# OUTPUT_CONNECTORS.net
KiCad netlist of a schematic drawn in Altium Designer
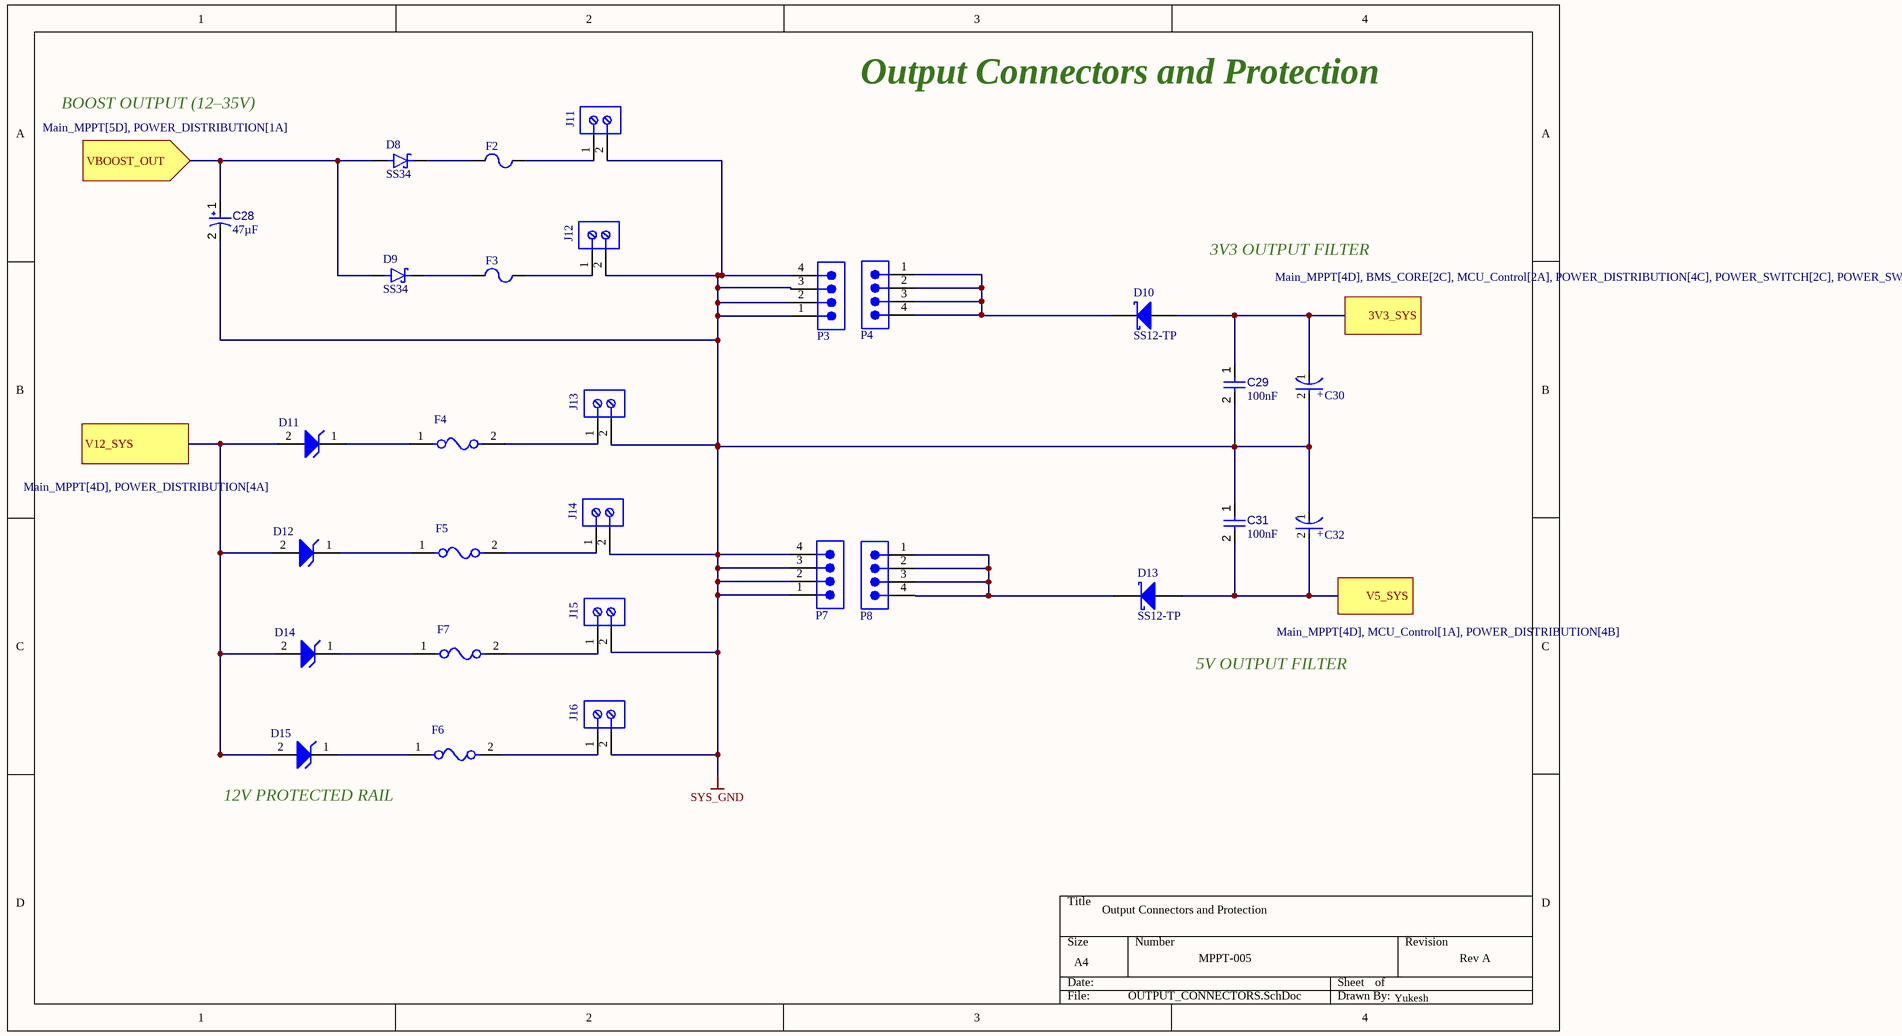
[diagram p0: OUTPUT_CONNECTORS.SchDoc]

(export (version "E")
  (design (tool "Eeschema 10.0.6"))
  (components
    (comp (ref "C28")
      (value "47µF")
      (footprint "CAPPR55-250-1120X630X1220")
      (description "Aluminum Electrolytic Capacitor, 47 uF, +/- 20%, 50 V, -40 to 85 degC, 2-Pin THD, RoHS, Bulk")
      (fields (field (name "MANUFACTURER") "Panasonic") (field (name "TOLERANCE") "20%"))
      (libsource (lib "YUKESH S") (part "CAP-P-2"))
    )
    (comp (ref "C29")
      (value "100nF")
      (footprint "CAPC0402(1005)60_L")
      (description "Chip Capacitor, 100nF +/-20%, 25V, 0402, Thickness 0.6 mm")
      (fields (field (name "TOLERANCE") "10%") (field (name "Comment") "Capacitor 100nF +/-20% 25V 0402"))
      (libsource (lib "YUKESH S") (part "CAP-NP-2"))
    )
    (comp (ref "C30")
      (value "F980J106MMA")
      (footprint "FP-F98M-MFG")
      (description "CAP TANT 10UF 20% 6.3V 0603")
      (fields
        (field (name "OCTOPART") "https://octopart.com/f980j106mma-nichicon-220777")
        (field (name "TOLERANCE") "20%")
      )
      (libsource (lib "Altium Content Vault") (part "cf48714ba7e38822c1575c7ec0b6d1f"))
    )
    (comp (ref "C31")
      (value "100nF")
      (footprint "CAPC0402(1005)60_L")
      (description "Chip Capacitor, 100nF +/-20%, 25V, 0402, Thickness 0.6 mm")
      (fields (field (name "TOLERANCE") "10%") (field (name "Comment") "Capacitor 100nF +/-20% 25V 0402"))
      (libsource (lib "YUKESH S") (part "CAP-NP-2"))
    )
    (comp (ref "C32")
      (value "F980J106MMA")
      (footprint "FP-F98M-MFG")
      (description "CAP TANT 10UF 20% 6.3V 0603")
      (fields
        (field (name "OCTOPART") "https://octopart.com/f980j106mma-nichicon-220777")
        (field (name "TOLERANCE") "20%")
      )
      (libsource (lib "Altium Content Vault") (part "cf48714ba7e38822c1575c7ec0b6d1f"))
    )
    (comp (ref "D8")
      (value "SS34")
      (footprint "Copy of DIOM7959X265N")
      (description "Diode Schottky 40 V 3A Surface Mount SMC (DO-214AB)")
      (fields (field (name "MF") "onsemi"))
      (libsource (lib "YUKESH S") (part "SS34"))
    )
    (comp (ref "D9")
      (value "SS34")
      (footprint "Copy of DIOM7959X265N")
      (description "Diode Schottky 40 V 3A Surface Mount SMC (DO-214AB)")
      (fields (field (name "MF") "onsemi"))
      (libsource (lib "YUKESH S") (part "SS34"))
    )
    (comp (ref "D10")
      (value "SS12-TP")
      (footprint "MCC-DO-214AC-2_V")
      (description "Schottky Rectifier, 20 V, 1 A, -55 to 125 degC, 2-Pin DO-214AC, RoHS, Tape and Reel")
      (fields (field (name "MANUFACTURER") "Micro Commercial Components"))
      (libsource (lib "YUKESH S") (part "DSKY-AK-2"))
    )
    (comp (ref "D11")
      (value "824500600")
      (footprint "WE-TVSP_DO-214AC_Unidirectional")
      (description "TVS diode [Würth Elektronik] 824500600 TVS diode")
      (libsource (lib "Altium Content Vault") (part "WE-TVSP_Unidirectional"))
    )
    (comp (ref "D12")
      (value "824500600")
      (footprint "WE-TVSP_DO-214AC_Unidirectional")
      (description "TVS diode [Würth Elektronik] 824500600 TVS diode")
      (libsource (lib "Altium Content Vault") (part "WE-TVSP_Unidirectional"))
    )
    (comp (ref "D13")
      (value "SS12-TP")
      (footprint "MCC-DO-214AC-2_V")
      (description "Schottky Rectifier, 20 V, 1 A, -55 to 125 degC, 2-Pin DO-214AC, RoHS, Tape and Reel")
      (fields (field (name "MANUFACTURER") "Micro Commercial Components"))
      (libsource (lib "YUKESH S") (part "DSKY-AK-2"))
    )
    (comp (ref "D14")
      (value "824500600")
      (footprint "WE-TVSP_DO-214AC_Unidirectional")
      (description "TVS diode [Würth Elektronik] 824500600 TVS diode")
      (libsource (lib "Altium Content Vault") (part "WE-TVSP_Unidirectional"))
    )
    (comp (ref "D15")
      (value "824500600")
      (footprint "WE-TVSP_DO-214AC_Unidirectional")
      (description "TVS diode [Würth Elektronik] 824500600 TVS diode")
      (libsource (lib "Altium Content Vault") (part "WE-TVSP_Unidirectional"))
    )
    (comp (ref "F2")
      (value "0154001.DR")
      (footprint "LFUS-0154001.DR_V")
      (description "Very Fast-Acting Fuse, 1 A, -55 to 125 degC, 2-Pin SMD, RoHS, Tape and Reel")
      (fields (field (name "MANUFACTURER") "Littelfuse"))
      (libsource (lib "Altium Content Vault") (part "FUSE-2"))
    )
    (comp (ref "F3")
      (value "0154001.DR")
      (footprint "LFUS-0154001.DR_V")
      (description "Very Fast-Acting Fuse, 1 A, -55 to 125 degC, 2-Pin SMD, RoHS, Tape and Reel")
      (fields (field (name "MANUFACTURER") "Littelfuse"))
      (libsource (lib "Altium Content Vault") (part "FUSE-2"))
    )
    (comp (ref "F4")
      (value "02810005H")
      (footprint "FP-02810005H-MFG")
      (description "FUSE HLDR RADIAL 125V 5A PNL MNT")
      (fields
        (field (name "OCTOPART") "https://octopart.com/02810005h-littelfuse-557282")
        (field (name "MANUFACTURER") "Littelfuse")
      )
      (libsource (lib "Altium Content Vault") (part "5bcf9b9f640e542cf0359d10258e979"))
    )
    (comp (ref "F5")
      (value "02810005H")
      (footprint "FP-02810005H-MFG")
      (description "FUSE HLDR RADIAL 125V 5A PNL MNT")
      (fields
        (field (name "OCTOPART") "https://octopart.com/02810005h-littelfuse-557282")
        (field (name "MANUFACTURER") "Littelfuse")
      )
      (libsource (lib "Altium Content Vault") (part "5bcf9b9f640e542cf0359d10258e979"))
    )
    (comp (ref "F6")
      (value "02810005H")
      (footprint "FP-02810005H-MFG")
      (description "FUSE HLDR RADIAL 125V 5A PNL MNT")
      (fields
        (field (name "OCTOPART") "https://octopart.com/02810005h-littelfuse-557282")
        (field (name "MANUFACTURER") "Littelfuse")
      )
      (libsource (lib "Altium Content Vault") (part "5bcf9b9f640e542cf0359d10258e979"))
    )
    (comp (ref "F7")
      (value "02810005H")
      (footprint "FP-02810005H-MFG")
      (description "FUSE HLDR RADIAL 125V 5A PNL MNT")
      (fields
        (field (name "OCTOPART") "https://octopart.com/02810005h-littelfuse-557282")
        (field (name "MANUFACTURER") "Littelfuse")
      )
      (libsource (lib "Altium Content Vault") (part "5bcf9b9f640e542cf0359d10258e979"))
    )
    (comp (ref "J11")
      (value "1714955")
      (footprint "PHOE-1714955_V")
      (description "PC Terminal Block, Pitch 6.35 mm, 1 x 2 Position, Height 21.5 mm, Tail Lenght 5.1 mm, RoHS, Bulk")
      (fields (field (name "MANUFACTURER") "Phoenix Contact"))
      (libsource (lib "") (part "CN-1P-F-TB2_1"))
    )
    (comp (ref "J12")
      (value "1714955")
      (footprint "PHOE-1714955_V")
      (description "PC Terminal Block, Pitch 6.35 mm, 1 x 2 Position, Height 21.5 mm, Tail Lenght 5.1 mm, RoHS, Bulk")
      (fields (field (name "MANUFACTURER") "Phoenix Contact"))
      (libsource (lib "Altium Content Vault") (part "CN-1P-F-TB2"))
    )
    (comp (ref "J13")
      (value "1714955")
      (footprint "PHOE-1714955_V")
      (description "PC Terminal Block, Pitch 6.35 mm, 1 x 2 Position, Height 21.5 mm, Tail Lenght 5.1 mm, RoHS, Bulk")
      (fields (field (name "MANUFACTURER") "Phoenix Contact"))
      (libsource (lib "Altium Content Vault") (part "CN-1P-F-TB2"))
    )
    (comp (ref "J14")
      (value "1714955")
      (footprint "PHOE-1714955_V")
      (description "PC Terminal Block, Pitch 6.35 mm, 1 x 2 Position, Height 21.5 mm, Tail Lenght 5.1 mm, RoHS, Bulk")
      (fields (field (name "MANUFACTURER") "Phoenix Contact"))
      (libsource (lib "Altium Content Vault") (part "CN-1P-F-TB2"))
    )
    (comp (ref "J15")
      (value "1714955")
      (footprint "PHOE-1714955_V")
      (description "PC Terminal Block, Pitch 6.35 mm, 1 x 2 Position, Height 21.5 mm, Tail Lenght 5.1 mm, RoHS, Bulk")
      (fields (field (name "MANUFACTURER") "Phoenix Contact"))
      (libsource (lib "Altium Content Vault") (part "CN-1P-F-TB2"))
    )
    (comp (ref "J16")
      (value "1714955")
      (footprint "PHOE-1714955_V")
      (description "PC Terminal Block, Pitch 6.35 mm, 1 x 2 Position, Height 21.5 mm, Tail Lenght 5.1 mm, RoHS, Bulk")
      (fields (field (name "MANUFACTURER") "Phoenix Contact"))
      (libsource (lib "Altium Content Vault") (part "CN-1P-F-TB2"))
    )
    (comp (ref "P3")
      (value "TSW-104-08-G-S")
      (footprint "SMTC-TSW-104-08-X-S")
      (description "0.025\" SQ Post Header, Through-hole, Vertical, -55 to 125 degC, 2.54 mm Pitch, 4-Pin, Male, RoHS")
      (fields (field (name "MANUFACTURER") "Samtec"))
      (libsource (lib "Altium Content Vault") (part "SMTC-TSW-104-08-X-S"))
    )
    (comp (ref "P4")
      (value "TSW-104-08-G-S")
      (footprint "SMTC-TSW-104-08-X-S")
      (description "0.025\" SQ Post Header, Through-hole, Vertical, -55 to 125 degC, 2.54 mm Pitch, 4-Pin, Male, RoHS")
      (fields (field (name "MANUFACTURER") "Samtec"))
      (libsource (lib "Altium Content Vault") (part "SMTC-TSW-104-08-X-S"))
    )
    (comp (ref "P7")
      (value "TSW-104-08-G-S")
      (footprint "SMTC-TSW-104-08-X-S")
      (description "0.025\" SQ Post Header, Through-hole, Vertical, -55 to 125 degC, 2.54 mm Pitch, 4-Pin, Male, RoHS")
      (fields (field (name "MANUFACTURER") "Samtec"))
      (libsource (lib "Altium Content Vault") (part "SMTC-TSW-104-08-X-S"))
    )
    (comp (ref "P8")
      (value "TSW-104-08-G-S")
      (footprint "SMTC-TSW-104-08-X-S")
      (description "0.025\" SQ Post Header, Through-hole, Vertical, -55 to 125 degC, 2.54 mm Pitch, 4-Pin, Male, RoHS")
      (fields (field (name "MANUFACTURER") "Samtec"))
      (libsource (lib "Altium Content Vault") (part "SMTC-TSW-104-08-X-S"))
    )
  )
  (nets
    (net (code "1") (name "/3V3_SYS") (class "Default")
      (node (ref "C29") (pin "1") (pinfunction "1_1") (pintype "passive"))
      (node (ref "C30") (pin "1") (pinfunction "C_1") (pintype "passive"))
      (node (ref "D10") (pin "1") (pinfunction "A_1") (pintype "passive"))
    )
    (net (code "2") (name "/V5_SYS") (class "Default")
      (node (ref "C31") (pin "2") (pinfunction "2_2") (pintype "passive"))
      (node (ref "C32") (pin "2") (pinfunction "A_2") (pintype "passive"))
      (node (ref "D13") (pin "1") (pinfunction "A_1") (pintype "passive"))
    )
    (net (code "3") (name "/V12_SYS") (class "Default")
      (node (ref "D11") (pin "2") (pinfunction "A_2") (pintype "passive"))
      (node (ref "D12") (pin "2") (pinfunction "A_2") (pintype "passive"))
      (node (ref "D14") (pin "2") (pinfunction "A_2") (pintype "passive"))
      (node (ref "D15") (pin "2") (pinfunction "A_2") (pintype "passive"))
    )
    (net (code "4") (name "/VBOOST_OUT") (class "Default")
      (node (ref "C28") (pin "1") (pinfunction "1_1") (pintype "passive"))
      (node (ref "D8") (pin "A") (pinfunction "A_A") (pintype "passive"))
      (node (ref "D9") (pin "A") (pinfunction "A_A") (pintype "passive"))
    )
    (net (code "5") (name "Net-(D8-K)") (class "Default")
      (node (ref "D8") (pin "C") (pinfunction "K_C") (pintype "passive"))
      (node (ref "F2") (pin "1") (pinfunction "1_1") (pintype "passive"))
    )
    (net (code "6") (name "Net-(D9-K)") (class "Default")
      (node (ref "D9") (pin "C") (pinfunction "K_C") (pintype "passive"))
      (node (ref "F3") (pin "1") (pinfunction "1_1") (pintype "passive"))
    )
    (net (code "7") (name "Net-(D10-K)") (class "Default")
      (node (ref "D10") (pin "2") (pinfunction "K_2") (pintype "passive"))
      (node (ref "P4") (pin "1") (pinfunction "1_1") (pintype "passive"))
      (node (ref "P4") (pin "2") (pinfunction "2_2") (pintype "passive"))
      (node (ref "P4") (pin "3") (pinfunction "3_3") (pintype "passive"))
      (node (ref "P4") (pin "4") (pinfunction "4_4") (pintype "passive"))
    )
    (net (code "8") (name "Net-(D11-K)") (class "Default")
      (node (ref "D11") (pin "1") (pinfunction "K_1") (pintype "passive"))
      (node (ref "F4") (pin "1") (pinfunction "1_1") (pintype "passive"))
    )
    (net (code "9") (name "Net-(D12-K)") (class "Default")
      (node (ref "D12") (pin "1") (pinfunction "K_1") (pintype "passive"))
      (node (ref "F5") (pin "1") (pinfunction "1_1") (pintype "passive"))
    )
    (net (code "10") (name "Net-(D13-K)") (class "Default")
      (node (ref "D13") (pin "2") (pinfunction "K_2") (pintype "passive"))
      (node (ref "P8") (pin "1") (pinfunction "1_1") (pintype "passive"))
      (node (ref "P8") (pin "2") (pinfunction "2_2") (pintype "passive"))
      (node (ref "P8") (pin "3") (pinfunction "3_3") (pintype "passive"))
      (node (ref "P8") (pin "4") (pinfunction "4_4") (pintype "passive"))
    )
    (net (code "11") (name "Net-(D14-K)") (class "Default")
      (node (ref "D14") (pin "1") (pinfunction "K_1") (pintype "passive"))
      (node (ref "F7") (pin "1") (pinfunction "1_1") (pintype "passive"))
    )
    (net (code "12") (name "Net-(D15-K)") (class "Default")
      (node (ref "D15") (pin "1") (pinfunction "K_1") (pintype "passive"))
      (node (ref "F6") (pin "1") (pinfunction "1_1") (pintype "passive"))
    )
    (net (code "13") (name "Net-(F2-Pad2)") (class "Default")
      (node (ref "F2") (pin "2") (pinfunction "2_2") (pintype "passive"))
      (node (ref "J11") (pin "1") (pinfunction "1_1") (pintype "passive"))
    )
    (net (code "14") (name "Net-(F3-Pad2)") (class "Default")
      (node (ref "F3") (pin "2") (pinfunction "2_2") (pintype "passive"))
      (node (ref "J12") (pin "1") (pinfunction "1_1") (pintype "passive"))
    )
    (net (code "15") (name "Net-(F4-Pad2)") (class "Default")
      (node (ref "F4") (pin "2") (pinfunction "2_2") (pintype "passive"))
      (node (ref "J13") (pin "1") (pinfunction "1_1") (pintype "passive"))
    )
    (net (code "16") (name "Net-(F5-Pad2)") (class "Default")
      (node (ref "F5") (pin "2") (pinfunction "2_2") (pintype "passive"))
      (node (ref "J14") (pin "1") (pinfunction "1_1") (pintype "passive"))
    )
    (net (code "17") (name "Net-(F6-Pad2)") (class "Default")
      (node (ref "F6") (pin "2") (pinfunction "2_2") (pintype "passive"))
      (node (ref "J16") (pin "1") (pinfunction "1_1") (pintype "passive"))
    )
    (net (code "18") (name "Net-(F7-Pad2)") (class "Default")
      (node (ref "F7") (pin "2") (pinfunction "2_2") (pintype "passive"))
      (node (ref "J15") (pin "1") (pinfunction "1_1") (pintype "passive"))
    )
    (net (code "19") (name "SYS_GND") (class "Default")
      (node (ref "C28") (pin "2") (pinfunction "2_2") (pintype "passive"))
      (node (ref "C29") (pin "2") (pinfunction "2_2") (pintype "passive"))
      (node (ref "C30") (pin "2") (pinfunction "A_2") (pintype "passive"))
      (node (ref "C31") (pin "1") (pinfunction "1_1") (pintype "passive"))
      (node (ref "C32") (pin "1") (pinfunction "C_1") (pintype "passive"))
      (node (ref "J11") (pin "2") (pinfunction "2_2") (pintype "passive"))
      (node (ref "J12") (pin "2") (pinfunction "2_2") (pintype "passive"))
      (node (ref "J13") (pin "2") (pinfunction "2_2") (pintype "passive"))
      (node (ref "J14") (pin "2") (pinfunction "2_2") (pintype "passive"))
      (node (ref "J15") (pin "2") (pinfunction "2_2") (pintype "passive"))
      (node (ref "J16") (pin "2") (pinfunction "2_2") (pintype "passive"))
      (node (ref "P3") (pin "1") (pinfunction "1_1") (pintype "passive"))
      (node (ref "P3") (pin "2") (pinfunction "2_2") (pintype "passive"))
      (node (ref "P3") (pin "3") (pinfunction "3_3") (pintype "passive"))
      (node (ref "P3") (pin "4") (pinfunction "4_4") (pintype "passive"))
      (node (ref "P7") (pin "1") (pinfunction "1_1") (pintype "passive"))
      (node (ref "P7") (pin "2") (pinfunction "2_2") (pintype "passive"))
      (node (ref "P7") (pin "3") (pinfunction "3_3") (pintype "passive"))
      (node (ref "P7") (pin "4") (pinfunction "4_4") (pintype "passive"))
    )
  )
)
